# ECGAquisitionBoard.net
KiCad netlist of a schematic drawn in Altium Designer
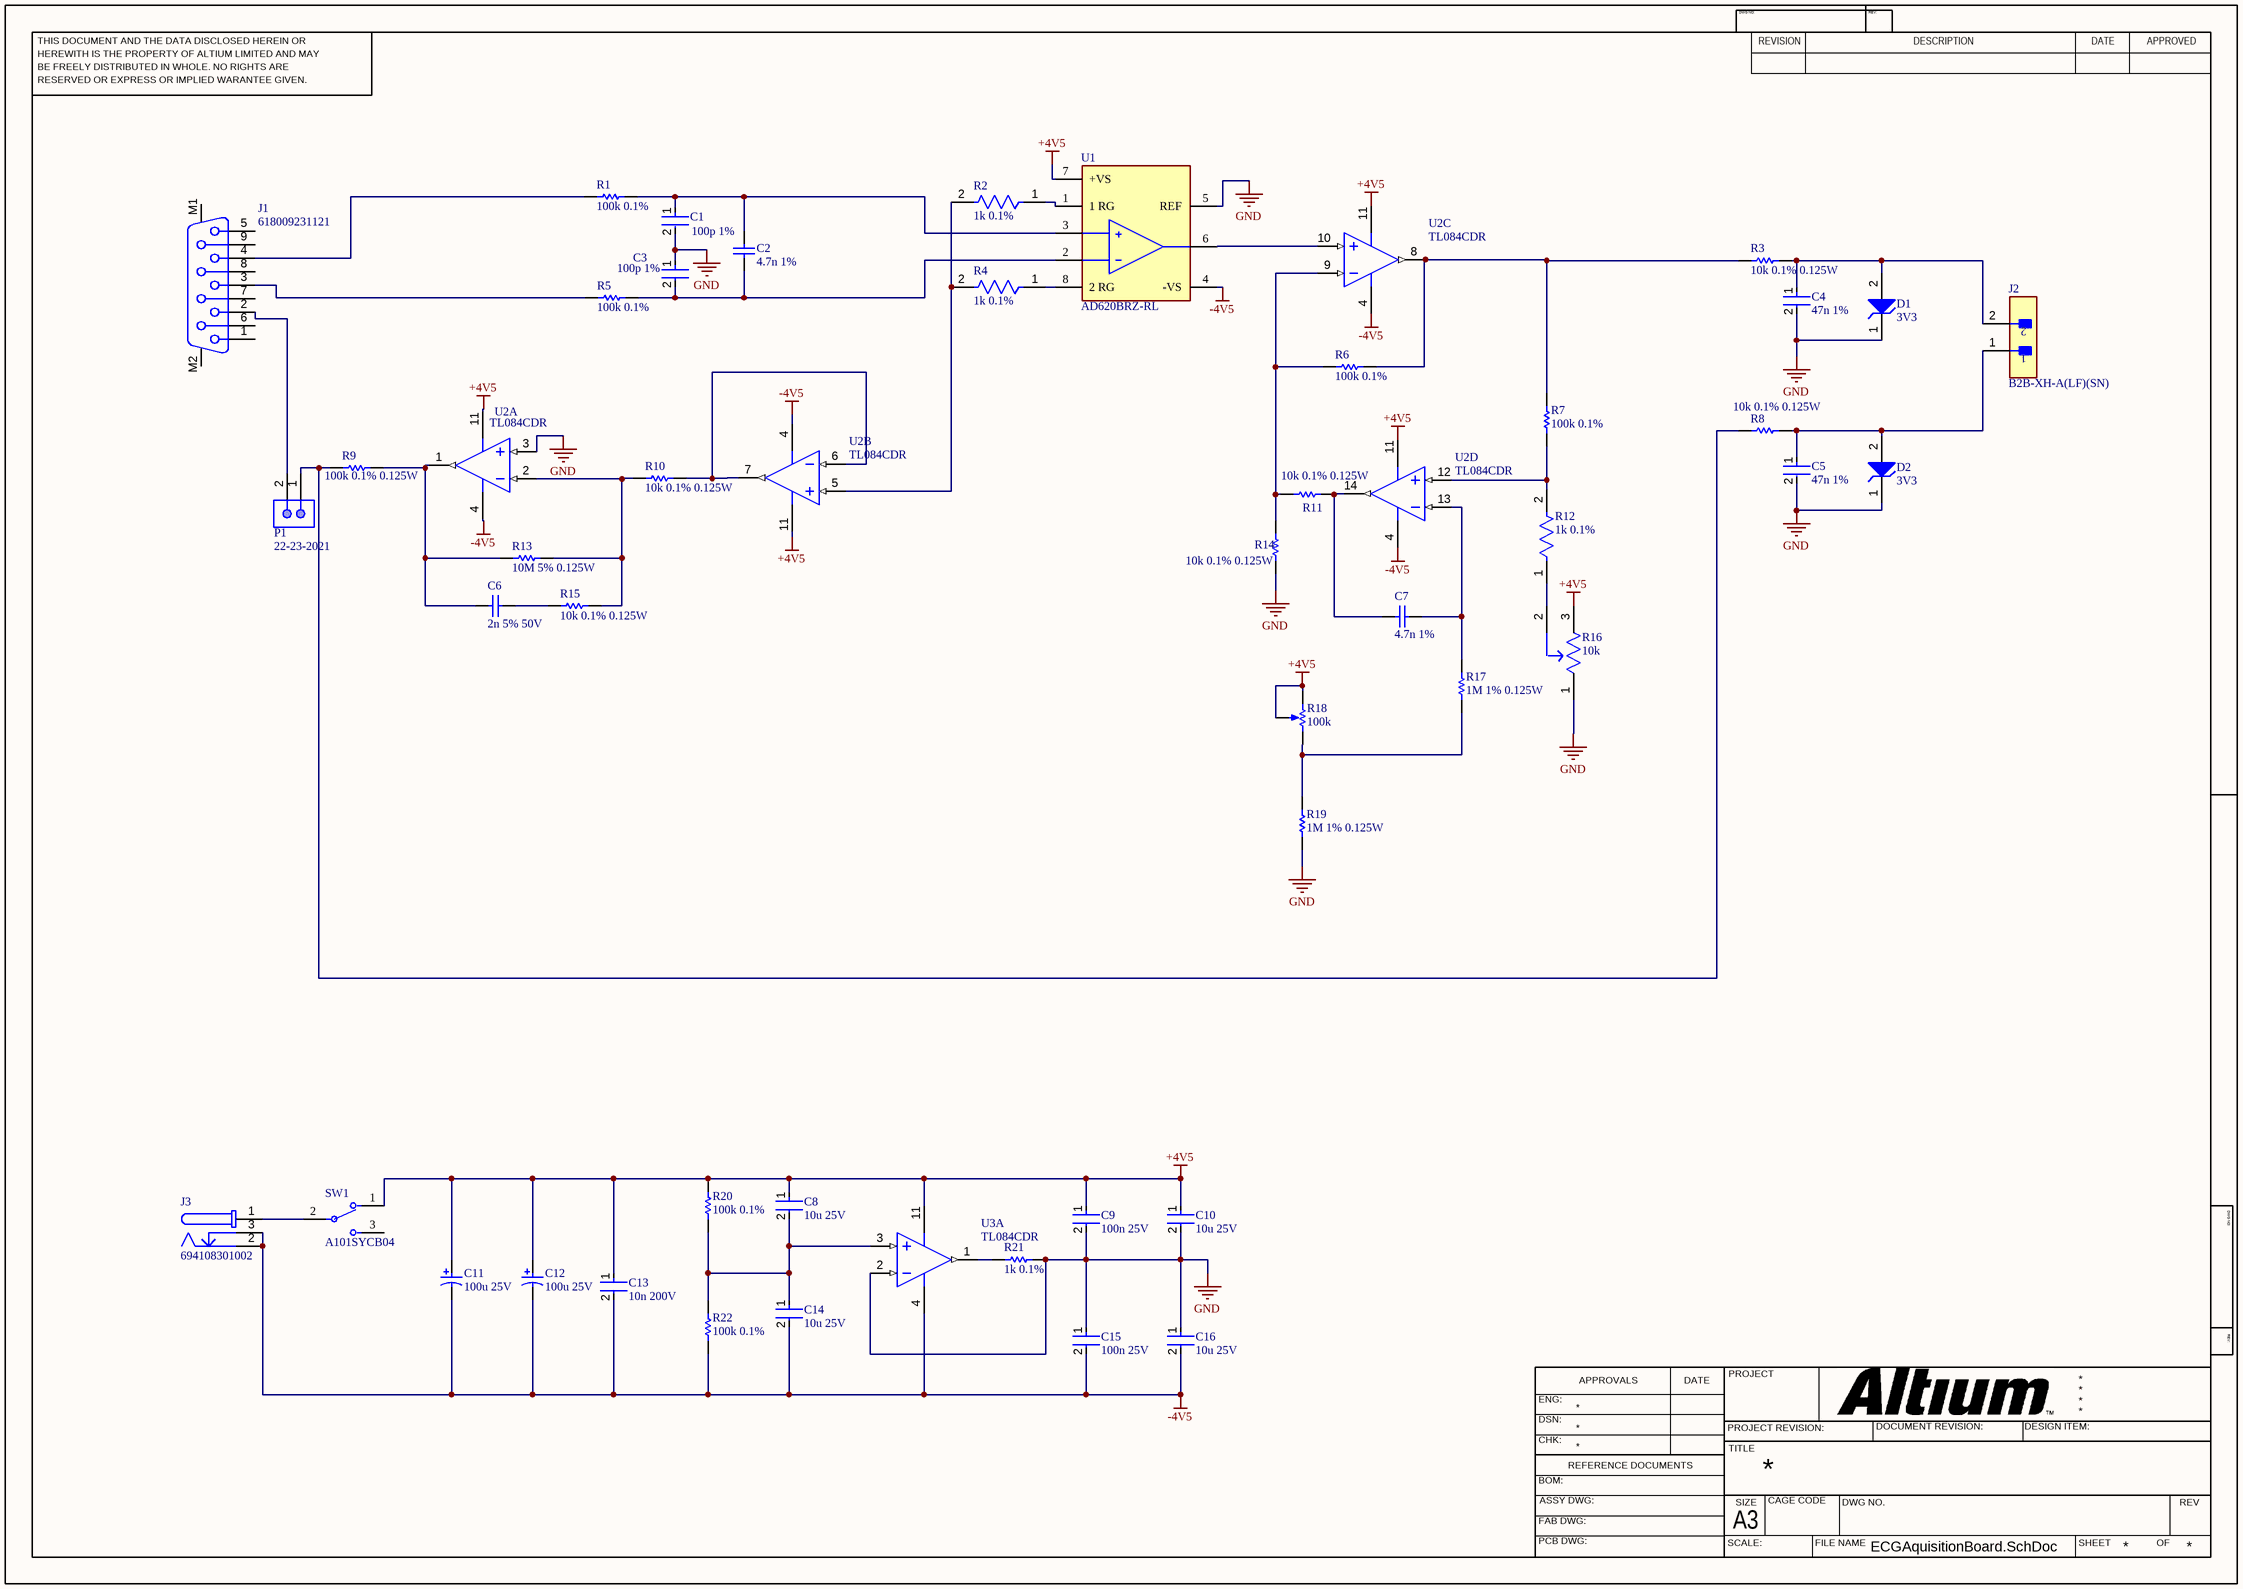
[diagram p0: ECGAquisitionBoard.SchDoc]

(export (version "E")
  (design (tool "Eeschema 10.0.6"))
  (components
    (comp (ref "C1")
      (value "100p 1%")
      (footprint "FP-0805-L_2_01_0_2-W_1_25-IPC_B")
      (description "General Purpose Ceramic Capacitor, 0805, 100pF, 1%, C0G, 30ppm/°C, 100V")
      (fields (field (name "TOLERANCE") "1%") (field (name "VOLTAGE") "100V"))
      (libsource (lib "Altium Content Vault") (part "02cd4be3c70576c341d710602a673aa"))
    )
    (comp (ref "C2")
      (value "4.7n 1%")
      (footprint "CAPC2013X94X50ML20T25")
      (fields
        (field (name "PART NUMBER") "08053A472FAT2A")
        (field (name "MANUFACTURER") "AVX Interconnect / Elco")
      )
      (libsource (lib "Altium Content Vault") (part "CAP"))
    )
    (comp (ref "C3")
      (value "100p 1%")
      (footprint "FP-0805-L_2_01_0_2-W_1_25-IPC_B")
      (description "General Purpose Ceramic Capacitor, 0805, 100pF, 1%, C0G, 30ppm/°C, 100V")
      (fields (field (name "TOLERANCE") "1%") (field (name "VOLTAGE") "100V"))
      (libsource (lib "Altium Content Vault") (part "02cd4be3c70576c341d710602a673aa"))
    )
    (comp (ref "C4")
      (value "47n 1%")
      (footprint "FP-C1206C-EB-MFG")
      (description "C1206 47,000 pF C0G 1.00% 50 V")
      (fields (field (name "TOLERANCE") "0.01"))
      (libsource (lib "Altium Content Vault") (part "b4654b650e69147ec39a6b967a45e02"))
    )
    (comp (ref "C5")
      (value "47n 1%")
      (footprint "FP-C1206C-EB-MFG")
      (description "C1206 47,000 pF C0G 1.00% 50 V")
      (fields (field (name "TOLERANCE") "0.01"))
      (libsource (lib "Altium Content Vault") (part "b4654b650e69147ec39a6b967a45e02"))
    )
    (comp (ref "C6")
      (value "2n 5% 50V")
      (footprint "CAPC2013X70X45NL10T25")
      (fields (field (name "PART NUMBER") "GRM2165C1H202JA01D") (field (name "MANUFACTURER") "Murata"))
      (libsource (lib "Altium Content Vault") (part "CAP"))
    )
    (comp (ref "C7")
      (value "4.7n 1%")
      (footprint "CAPC2013X94X50ML20T25")
      (fields
        (field (name "PART NUMBER") "08053A472FAT2A")
        (field (name "MANUFACTURER") "AVX Interconnect / Elco")
      )
      (libsource (lib "Altium Content Vault") (part "CAP"))
    )
    (comp (ref "C8")
      (value "10u 25V")
      (footprint "FP-GRM21B-0_15-IPC_C")
      (description "Chip Multilayer Ceramic Capacitors for General Purpose, 0805, 10uF, X5R, 15%, 10%, 25V")
      (fields (field (name "VOLTAGE") "25V") (field (name "TOLERANCE") "10%"))
      (libsource (lib "Altium Content Vault") (part "b4654b650e69147ec39a6b967a45e02"))
    )
    (comp (ref "C9")
      (value "100n 25V")
      (footprint "FP-C0805C-DN-MFG")
      (description "C0805 0.10 μF X7R 30ppm/°C 20.00% 25 V")
      (fields (field (name "TOLERANCE") "0.2"))
      (libsource (lib "Altium Content Vault") (part "b4654b650e69147ec39a6b967a45e02"))
    )
    (comp (ref "C10")
      (value "10u 25V")
      (footprint "FP-GRM21B-0_15-IPC_C")
      (description "Chip Multilayer Ceramic Capacitors for General Purpose, 0805, 10uF, X5R, 15%, 10%, 25V")
      (fields (field (name "VOLTAGE") "25V") (field (name "TOLERANCE") "10%"))
      (libsource (lib "Altium Content Vault") (part "b4654b650e69147ec39a6b967a45e02"))
    )
    (comp (ref "C11")
      (value "100u 25V")
      (footprint "PNSC-FK-V-D8_V")
      (fields (field (name "MANUFACTURER") "Panasonic"))
      (libsource (lib "Altium Content Vault") (part "CAP-P-2"))
    )
    (comp (ref "C12")
      (value "100u 25V")
      (footprint "PNSC-FK-V-D8_V")
      (fields (field (name "MANUFACTURER") "Panasonic"))
      (libsource (lib "Altium Content Vault") (part "CAP-P-2"))
    )
    (comp (ref "C13")
      (value "10n 200V")
      (footprint "FP-0805-L_2_01_0_2-W_1_25-IPC_A")
      (description "General Purpose Ceramic Capacitor, 0805, 10nF, 10%, X7R, 0.15, 200V")
      (fields (field (name "VOLTAGE") "200V") (field (name "TOLERANCE") "10%"))
      (libsource (lib "Altium Content Vault") (part "02cd4be3c70576c341d710602a673aa"))
    )
    (comp (ref "C14")
      (value "10u 25V")
      (footprint "FP-GRM21B-0_15-IPC_C")
      (description "Chip Multilayer Ceramic Capacitors for General Purpose, 0805, 10uF, X5R, 15%, 10%, 25V")
      (fields (field (name "VOLTAGE") "25V") (field (name "TOLERANCE") "10%"))
      (libsource (lib "Altium Content Vault") (part "b4654b650e69147ec39a6b967a45e02"))
    )
    (comp (ref "C15")
      (value "100n 25V")
      (footprint "FP-C0805C-DN-MFG")
      (description "C0805 0.10 μF X7R 30ppm/°C 20.00% 25 V")
      (fields (field (name "TOLERANCE") "0.2"))
      (libsource (lib "Altium Content Vault") (part "b4654b650e69147ec39a6b967a45e02"))
    )
    (comp (ref "C16")
      (value "10u 25V")
      (footprint "FP-GRM21B-0_15-IPC_C")
      (description "Chip Multilayer Ceramic Capacitors for General Purpose, 0805, 10uF, X5R, 15%, 10%, 25V")
      (fields (field (name "VOLTAGE") "25V") (field (name "TOLERANCE") "10%"))
      (libsource (lib "Altium Content Vault") (part "b4654b650e69147ec39a6b967a45e02"))
    )
    (comp (ref "D1")
      (value "3V3")
      (footprint "ONSC-SOD-123-2-425-04_V")
      (description "Zener Voltage Regulator, 500 mW, 2-Pin SOD-123, Pb-Free, Tape and Reel")
      (fields (field (name "PARTNUMBER") "MMSZ5226BT1G") (field (name "MANUFACTURER") "On Semiconductor"))
      (libsource (lib "Altium Content Vault") (part "ONSC-K1A2-2"))
    )
    (comp (ref "D2")
      (value "3V3")
      (footprint "ONSC-SOD-123-2-425-04_V")
      (description "Zener Voltage Regulator, 500 mW, 2-Pin SOD-123, Pb-Free, Tape and Reel")
      (fields (field (name "PARTNUMBER") "MMSZ5226BT1G") (field (name "MANUFACTURER") "On Semiconductor"))
      (libsource (lib "Altium Content Vault") (part "ONSC-K1A2-2"))
    )
    (comp (ref "J1")
      (value "618009231121")
      (footprint "618009231121")
      (libsource (lib "Altium Content Vault") (part "D-Sub_Female_09p"))
    )
    (comp (ref "J2")
      (value "B2B-XH-A(LF)(SN)")
      (footprint "FP-B2B-XH-A_LF_SN-MFG")
      (description "CONN HEADER VERT 2POS 2.5MM")
      (libsource (lib "Altium Content Vault") (part "3bc925449376181038e59eaffc5286c"))
    )
    (comp (ref "J3")
      (value "694108301002")
      (footprint "694108301002")
      (libsource (lib "Altium Content Vault") (part "DC Power Jack"))
    )
    (comp (ref "P1")
      (value "22-23-2021")
      (footprint "MOLX-22-23-2021_V")
      (libsource (lib "Altium Content Vault") (part "CN-1P-M-R2"))
    )
    (comp (ref "R1")
      (value "100k 0.1%")
      (footprint "RESC2013X60X40LL20T25_A")
      (fields (field (name "TOLERANCE") "0.1%") (field (name "MANUFACTURER") "Panasonic"))
      (libsource (lib "Altium Content Vault") (part "RES-2"))
    )
    (comp (ref "R2")
      (value "1k 0.1%")
      (footprint "FP-ERA6A-IPC_C")
      (description "RES 1K OHM 0.1% 1/8W 0805")
      (fields (field (name "TOLERANCE") "0.1%"))
      (libsource (lib "Altium Content Vault") (part "1029c3af85768c4190bb7ad29bc67b5"))
    )
    (comp (ref "R3")
      (value "10k 0.1% 0.125W")
      (footprint "RESC2013X60X40LL20T25_A")
      (fields (field (name "TOLERANCE") "0.1%") (field (name "MANUFACTURER") "Panasonic"))
      (libsource (lib "Altium Content Vault") (part "RES-2"))
    )
    (comp (ref "R4")
      (value "1k 0.1%")
      (footprint "FP-ERA6A-IPC_C")
      (description "RES 1K OHM 0.1% 1/8W 0805")
      (fields (field (name "TOLERANCE") "0.1%"))
      (libsource (lib "Altium Content Vault") (part "1029c3af85768c4190bb7ad29bc67b5"))
    )
    (comp (ref "R5")
      (value "100k 0.1%")
      (footprint "RESC2013X60X40LL20T25_A")
      (fields (field (name "TOLERANCE") "0.1%") (field (name "MANUFACTURER") "Panasonic"))
      (libsource (lib "Altium Content Vault") (part "RES-2"))
    )
    (comp (ref "R6")
      (value "100k 0.1%")
      (footprint "RESC2013X60X40LL20T25_A")
      (fields (field (name "TOLERANCE") "0.1%") (field (name "MANUFACTURER") "Panasonic"))
      (libsource (lib "Altium Content Vault") (part "RES-2"))
    )
    (comp (ref "R7")
      (value "100k 0.1%")
      (footprint "RESC2013X60X40LL20T25_A")
      (fields (field (name "TOLERANCE") "0.1%") (field (name "MANUFACTURER") "Panasonic"))
      (libsource (lib "Altium Content Vault") (part "RES-2"))
    )
    (comp (ref "R8")
      (value "10k 0.1% 0.125W")
      (footprint "RESC2013X60X40LL20T25_A")
      (fields (field (name "TOLERANCE") "0.1%") (field (name "MANUFACTURER") "Panasonic"))
      (libsource (lib "Altium Content Vault") (part "RES-2"))
    )
    (comp (ref "R9")
      (value "100k 0.1% 0.125W")
      (footprint "RESC2013X60X40LL20T25_A")
      (fields (field (name "TOLERANCE") "0.1%") (field (name "MANUFACTURER") "Panasonic"))
      (libsource (lib "Altium Content Vault") (part "RES-2"))
    )
    (comp (ref "R10")
      (value "10k 0.1% 0.125W")
      (footprint "RESC2013X60X40LL20T25_A")
      (fields (field (name "TOLERANCE") "0.1%") (field (name "MANUFACTURER") "Panasonic"))
      (libsource (lib "Altium Content Vault") (part "RES-2"))
    )
    (comp (ref "R11")
      (value "10k 0.1% 0.125W")
      (footprint "RESC2013X60X40LL20T25_A")
      (fields (field (name "TOLERANCE") "0.1%") (field (name "MANUFACTURER") "Panasonic"))
      (libsource (lib "Altium Content Vault") (part "RES-2"))
    )
    (comp (ref "R12")
      (value "1k 0.1%")
      (footprint "FP-ERA6A-IPC_C")
      (description "RES 1K OHM 0.1% 1/8W 0805")
      (fields (field (name "TOLERANCE") "0.1%"))
      (libsource (lib "Altium Content Vault") (part "1029c3af85768c4190bb7ad29bc67b5"))
    )
    (comp (ref "R13")
      (value "10M 5% 0.125W")
      (footprint "RESC2013X50X30LL20T20")
      (fields (field (name "PART NUMBER") "CRCW080510M0JNEA") (field (name "MANUFACTURER") "Vishay Dale"))
      (libsource (lib "Altium Content Vault") (part "RES"))
    )
    (comp (ref "R14")
      (value "10k 0.1% 0.125W")
      (footprint "RESC2013X60X40LL20T25_A")
      (fields (field (name "TOLERANCE") "0.1%") (field (name "MANUFACTURER") "Panasonic"))
      (libsource (lib "Altium Content Vault") (part "RES-2"))
    )
    (comp (ref "R15")
      (value "10k 0.1% 0.125W")
      (footprint "RESC2013X60X40LL20T25_A")
      (fields (field (name "TOLERANCE") "0.1%") (field (name "MANUFACTURER") "Panasonic"))
      (libsource (lib "Altium Content Vault") (part "RES-2"))
    )
    (comp (ref "R16")
      (value "10k")
      (footprint "FP-3266W-MFG")
      (description "TRIMMER 10K OHM 0.25W PC PIN TOP")
      (fields
        (field (name "MANUFACTURER") "Bourns")
        (field (name "OCTOPART") "https://octopart.com/3266w-1-103lf-bourns-81445")
      )
      (libsource (lib "Altium Content Vault") (part "5aa38b60e553f01fbee9df648f8b81b"))
    )
    (comp (ref "R17")
      (value "1M 1% 0.125W")
      (footprint "RESC3216X70X50NL05T20")
      (fields (field (name "PART NUMBER") "ERJ-8ENF1004V") (field (name "MANUFACTURER") "Panasonic"))
      (libsource (lib "Altium Content Vault") (part "RES"))
    )
    (comp (ref "R18")
      (value "100k")
      (footprint "BOUR-3266W-3_V")
      (description "Square Trimpot Trimming Potentiometer, 100 KOhm, 0.25 W, -55 to 125 degC, 3-Pin THD, RoHS, Tube")
      (fields (field (name "TOLERANCE") "+/-10%") (field (name "MANUFACTURER") "Bourns"))
      (libsource (lib "Altium Content Vault") (part "BOUR-POT-3"))
    )
    (comp (ref "R19")
      (value "1M 1% 0.125W")
      (footprint "RESC3216X70X50NL05T20")
      (fields (field (name "PART NUMBER") "ERJ-8ENF1004V") (field (name "MANUFACTURER") "Panasonic"))
      (libsource (lib "Altium Content Vault") (part "RES"))
    )
    (comp (ref "R20")
      (value "100k 0.1%")
      (footprint "RESC2013X60X40LL20T25_A")
      (fields (field (name "TOLERANCE") "0.1%") (field (name "MANUFACTURER") "Panasonic"))
      (libsource (lib "Altium Content Vault") (part "RES-2"))
    )
    (comp (ref "R21")
      (value "1k 0.1%")
      (footprint "RESC2013X60X40LL20T25_A")
      (fields (field (name "TOLERANCE") "0.1%") (field (name "MANUFACTURER") "Panasonic"))
      (libsource (lib "Altium Content Vault") (part "RES-2"))
    )
    (comp (ref "R22")
      (value "100k 0.1%")
      (footprint "RESC2013X60X40LL20T25_A")
      (fields (field (name "TOLERANCE") "0.1%") (field (name "MANUFACTURER") "Panasonic"))
      (libsource (lib "Altium Content Vault") (part "RES-2"))
    )
    (comp (ref "SW1")
      (value "A101SYCB04")
      (footprint "FP-A101SYCB04-MFG")
      (description "SWITCH TOGGLE SPDT 0.4VA 20V")
      (libsource (lib "Altium Content Vault") (part "52c419afdc2a387c7d548259a9aeefb"))
    )
    (comp (ref "U1")
      (value "AD620BRZ-RL")
      (footprint "FP-R-8-IPC_A")
      (description "IC INST AMP 1 CIRCUIT 8SOIC")
      (libsource (lib "Altium Content Vault") (part "b1ca39593d8cc57aa2599e6d86efae1"))
    )
    (comp (ref "U2")
      (value "TL084CDR")
      (footprint "D0014A_N")
      (fields (field (name "MANUFACTURER") "Texas Instruments"))
      (libsource (lib "Altium Content Vault") (part "TI-TLXX4X_MC3403-X14"))
    )
    (comp (ref "U3")
      (value "TL084CDR")
      (footprint "D0014A_N")
      (fields (field (name "MANUFACTURER") "Texas Instruments"))
      (libsource (lib "Altium Content Vault") (part "TI-TLXX4X_MC3403-X14"))
    )
  )
  (nets
    (net (code "1") (name "+4V5") (class "Default")
      (node (ref "C10") (pin "1") (pinfunction "1_1") (pintype "passive"))
      (node (ref "C11") (pin "1") (pinfunction "1_1") (pintype "passive"))
      (node (ref "C12") (pin "1") (pinfunction "1_1") (pintype "passive"))
      (node (ref "C13") (pin "1") (pinfunction "1_1") (pintype "passive"))
      (node (ref "C8") (pin "1") (pinfunction "1_1") (pintype "passive"))
      (node (ref "C9") (pin "1") (pinfunction "1_1") (pintype "passive"))
      (node (ref "R16") (pin "3") (pinfunction "CW_3") (pintype "passive"))
      (node (ref "R18") (pin "1") (pinfunction "CCW_1") (pintype "passive"))
      (node (ref "R18") (pin "2") (pinfunction "WIPER_2") (pintype "passive"))
      (node (ref "R20") (pin "2") (pinfunction "2_2") (pintype "passive"))
      (node (ref "SW1") (pin "1") (pinfunction "1_1") (pintype "passive"))
      (node (ref "U1") (pin "7") (pinfunction "+VS_7") (pintype "power_in"))
      (node (ref "U2") (pin "11") (pinfunction "VCC-_11") (pintype "power_in"))
      (node (ref "U3") (pin "11") (pinfunction "VCC-_11") (pintype "power_in"))
    )
    (net (code "2") (name "-4V5") (class "Default")
      (node (ref "C11") (pin "2") (pinfunction "2_2") (pintype "passive"))
      (node (ref "C12") (pin "2") (pinfunction "2_2") (pintype "passive"))
      (node (ref "C13") (pin "2") (pinfunction "2_2") (pintype "passive"))
      (node (ref "C14") (pin "2") (pinfunction "2_2") (pintype "passive"))
      (node (ref "C15") (pin "2") (pinfunction "2_2") (pintype "passive"))
      (node (ref "C16") (pin "2") (pinfunction "2_2") (pintype "passive"))
      (node (ref "J3") (pin "2") (pinfunction "2_2") (pintype "passive"))
      (node (ref "J3") (pin "3") (pinfunction "3_3") (pintype "passive"))
      (node (ref "R22") (pin "1") (pinfunction "1_1") (pintype "passive"))
      (node (ref "U1") (pin "4") (pinfunction "-VS_4") (pintype "power_in"))
      (node (ref "U2") (pin "4") (pinfunction "VCC+_4") (pintype "power_in"))
      (node (ref "U3") (pin "4") (pinfunction "VCC+_4") (pintype "power_in"))
    )
    (net (code "3") (name "GND") (class "Default")
      (node (ref "C1") (pin "2") (pinfunction "2_2") (pintype "passive"))
      (node (ref "C10") (pin "2") (pinfunction "2_2") (pintype "passive"))
      (node (ref "C15") (pin "1") (pinfunction "1_1") (pintype "passive"))
      (node (ref "C16") (pin "1") (pinfunction "1_1") (pintype "passive"))
      (node (ref "C3") (pin "1") (pinfunction "1_1") (pintype "passive"))
      (node (ref "C4") (pin "2") (pinfunction "2_2") (pintype "passive"))
      (node (ref "C5") (pin "2") (pinfunction "2_2") (pintype "passive"))
      (node (ref "C9") (pin "2") (pinfunction "2_2") (pintype "passive"))
      (node (ref "D1") (pin "1") (pinfunction "K_1") (pintype "passive"))
      (node (ref "D2") (pin "1") (pinfunction "K_1") (pintype "passive"))
      (node (ref "R14") (pin "1") (pinfunction "1_1") (pintype "passive"))
      (node (ref "R16") (pin "1") (pinfunction "CCW_1") (pintype "passive"))
      (node (ref "R19") (pin "1") (pinfunction "1_1") (pintype "passive"))
      (node (ref "R21") (pin "1") (pinfunction "1_1") (pintype "passive"))
      (node (ref "U1") (pin "5") (pinfunction "REF_5") (pintype "passive"))
      (node (ref "U2") (pin "3") (pinfunction "IN1+_3") (pintype "input"))
      (node (ref "U3") (pin "2") (pinfunction "IN1-_2") (pintype "input"))
    )
    (net (code "4") (name "Net-(C6-Pad2)") (class "Default")
      (node (ref "C6") (pin "2") (pinfunction "2_2") (pintype "passive"))
      (node (ref "R15") (pin "2") (pinfunction "2_2") (pintype "passive"))
    )
    (net (code "5") (name "Net-(D1-A)") (class "Default")
      (node (ref "C4") (pin "1") (pinfunction "1_1") (pintype "passive"))
      (node (ref "D1") (pin "2") (pinfunction "A_2") (pintype "passive"))
      (node (ref "J2") (pin "2") (pinfunction "2_2") (pintype "passive"))
      (node (ref "R3") (pin "1") (pinfunction "1_1") (pintype "passive"))
    )
    (net (code "6") (name "Net-(D2-A)") (class "Default")
      (node (ref "C5") (pin "1") (pinfunction "1_1") (pintype "passive"))
      (node (ref "D2") (pin "2") (pinfunction "A_2") (pintype "passive"))
      (node (ref "J2") (pin "1") (pinfunction "1_1") (pintype "passive"))
      (node (ref "R8") (pin "1") (pinfunction "1_1") (pintype "passive"))
    )
    (net (code "7") (name "Net-(J1-Pad2)") (class "Default")
      (node (ref "J1") (pin "2") (pinfunction "2_2") (pintype "passive"))
      (node (ref "P1") (pin "2") (pinfunction "2_2") (pintype "passive"))
    )
    (net (code "8") (name "Net-(J1-Pad3)") (class "Default")
      (node (ref "J1") (pin "3") (pinfunction "3_3") (pintype "passive"))
      (node (ref "R5") (pin "2") (pinfunction "2_2") (pintype "passive"))
    )
    (net (code "9") (name "Net-(J1-Pad4)") (class "Default")
      (node (ref "J1") (pin "4") (pinfunction "4_4") (pintype "passive"))
      (node (ref "R1") (pin "2") (pinfunction "2_2") (pintype "passive"))
    )
    (net (code "10") (name "Net-(J3-Pad1)") (class "Default")
      (node (ref "J3") (pin "1") (pinfunction "1_1") (pintype "passive"))
      (node (ref "SW1") (pin "2") (pinfunction "2_2") (pintype "passive"))
    )
    (net (code "11") (name "Net-(P1-Pad1)") (class "Default")
      (node (ref "P1") (pin "1") (pinfunction "1_1") (pintype "passive"))
      (node (ref "R8") (pin "2") (pinfunction "2_2") (pintype "passive"))
      (node (ref "R9") (pin "2") (pinfunction "2_2") (pintype "passive"))
    )
    (net (code "12") (name "Net-(R16-WIPER)") (class "Default")
      (node (ref "R12") (pin "1") (pinfunction "1_1") (pintype "passive"))
      (node (ref "R16") (pin "2") (pinfunction "WIPER_2") (pintype "passive"))
    )
    (net (code "13") (name "Net-(R18-CW)") (class "Default")
      (node (ref "R17") (pin "1") (pinfunction "1_1") (pintype "passive"))
      (node (ref "R18") (pin "3") (pinfunction "CW_3") (pintype "passive"))
      (node (ref "R19") (pin "2") (pinfunction "2_2") (pintype "passive"))
    )
    (net (code "14") (name "Net-(U1-+IN)") (class "Default")
      (node (ref "C1") (pin "1") (pinfunction "1_1") (pintype "passive"))
      (node (ref "C2") (pin "2") (pinfunction "2_2") (pintype "passive"))
      (node (ref "R1") (pin "1") (pinfunction "1_1") (pintype "passive"))
      (node (ref "U1") (pin "3") (pinfunction "+IN_3") (pintype "tri_state"))
    )
    (net (code "15") (name "Net-(U1--IN)") (class "Default")
      (node (ref "C2") (pin "1") (pinfunction "1_1") (pintype "passive"))
      (node (ref "C3") (pin "2") (pinfunction "2_2") (pintype "passive"))
      (node (ref "R5") (pin "1") (pinfunction "1_1") (pintype "passive"))
      (node (ref "U1") (pin "2") (pinfunction "-IN_2") (pintype "tri_state"))
    )
    (net (code "16") (name "Net-(U1-1_RG)") (class "Default")
      (node (ref "R2") (pin "1") (pinfunction "1_1") (pintype "passive"))
      (node (ref "U1") (pin "1") (pinfunction "1_RG_1") (pintype "passive"))
    )
    (net (code "17") (name "Net-(U1-2_RG)") (class "Default")
      (node (ref "R4") (pin "1") (pinfunction "1_1") (pintype "passive"))
      (node (ref "U1") (pin "8") (pinfunction "2_RG_8") (pintype "passive"))
    )
    (net (code "18") (name "Net-(U1-OUTPUT)") (class "Default")
      (node (ref "U1") (pin "6") (pinfunction "OUTPUT_6") (pintype "passive"))
      (node (ref "U2") (pin "10") (pinfunction "IN3+_10") (pintype "input"))
    )
    (net (code "19") (name "Net-(U2A-IN1-)") (class "Default")
      (node (ref "R10") (pin "2") (pinfunction "2_2") (pintype "passive"))
      (node (ref "R13") (pin "2") (pinfunction "2_2") (pintype "passive"))
      (node (ref "R15") (pin "1") (pinfunction "1_1") (pintype "passive"))
      (node (ref "U2") (pin "2") (pinfunction "IN1-_2") (pintype "input"))
    )
    (net (code "20") (name "Net-(U2A-OUT1)") (class "Default")
      (node (ref "C6") (pin "1") (pinfunction "1_1") (pintype "passive"))
      (node (ref "R13") (pin "1") (pinfunction "1_1") (pintype "passive"))
      (node (ref "R9") (pin "1") (pinfunction "1_1") (pintype "passive"))
      (node (ref "U2") (pin "1") (pinfunction "OUT1_1") (pintype "output"))
    )
    (net (code "21") (name "Net-(U2B-IN2+)") (class "Default")
      (node (ref "R2") (pin "2") (pinfunction "2_2") (pintype "passive"))
      (node (ref "R4") (pin "2") (pinfunction "2_2") (pintype "passive"))
      (node (ref "U2") (pin "5") (pinfunction "IN2+_5") (pintype "input"))
    )
    (net (code "22") (name "Net-(U2B-IN2-)") (class "Default")
      (node (ref "R10") (pin "1") (pinfunction "1_1") (pintype "passive"))
      (node (ref "U2") (pin "6") (pinfunction "IN2-_6") (pintype "input"))
      (node (ref "U2") (pin "7") (pinfunction "OUT2_7") (pintype "output"))
    )
    (net (code "23") (name "Net-(U2C-IN3-)") (class "Default")
      (node (ref "R11") (pin "2") (pinfunction "2_2") (pintype "passive"))
      (node (ref "R14") (pin "2") (pinfunction "2_2") (pintype "passive"))
      (node (ref "R6") (pin "2") (pinfunction "2_2") (pintype "passive"))
      (node (ref "U2") (pin "9") (pinfunction "IN3-_9") (pintype "input"))
    )
    (net (code "24") (name "Net-(U2C-OUT3)") (class "Default")
      (node (ref "R3") (pin "2") (pinfunction "2_2") (pintype "passive"))
      (node (ref "R6") (pin "1") (pinfunction "1_1") (pintype "passive"))
      (node (ref "R7") (pin "1") (pinfunction "1_1") (pintype "passive"))
      (node (ref "U2") (pin "8") (pinfunction "OUT3_8") (pintype "output"))
    )
    (net (code "25") (name "Net-(U2D-IN4+)") (class "Default")
      (node (ref "R12") (pin "2") (pinfunction "2_2") (pintype "passive"))
      (node (ref "R7") (pin "2") (pinfunction "2_2") (pintype "passive"))
      (node (ref "U2") (pin "12") (pinfunction "IN4+_12") (pintype "input"))
    )
    (net (code "26") (name "Net-(U2D-IN4-)") (class "Default")
      (node (ref "C7") (pin "1") (pinfunction "1_1") (pintype "passive"))
      (node (ref "R17") (pin "2") (pinfunction "2_2") (pintype "passive"))
      (node (ref "U2") (pin "13") (pinfunction "IN4-_13") (pintype "input"))
    )
    (net (code "27") (name "Net-(U2D-OUT4)") (class "Default")
      (node (ref "C7") (pin "2") (pinfunction "2_2") (pintype "passive"))
      (node (ref "R11") (pin "1") (pinfunction "1_1") (pintype "passive"))
      (node (ref "U2") (pin "14") (pinfunction "OUT4_14") (pintype "output"))
    )
    (net (code "28") (name "Net-(U3A-IN1+)") (class "Default")
      (node (ref "C14") (pin "1") (pinfunction "1_1") (pintype "passive"))
      (node (ref "C8") (pin "2") (pinfunction "2_2") (pintype "passive"))
      (node (ref "R20") (pin "1") (pinfunction "1_1") (pintype "passive"))
      (node (ref "R22") (pin "2") (pinfunction "2_2") (pintype "passive"))
      (node (ref "U3") (pin "3") (pinfunction "IN1+_3") (pintype "input"))
    )
    (net (code "29") (name "Net-(U3A-OUT1)") (class "Default")
      (node (ref "R21") (pin "2") (pinfunction "2_2") (pintype "passive"))
      (node (ref "U3") (pin "1") (pinfunction "OUT1_1") (pintype "output"))
    )
    (net (code "30") (name "unconnected-(J1-Pad1)") (class "Default")
      (node (ref "J1") (pin "1") (pinfunction "1_1") (pintype "passive"))
    )
    (net (code "31") (name "unconnected-(J1-Pad5)") (class "Default")
      (node (ref "J1") (pin "5") (pinfunction "5_5") (pintype "passive"))
    )
    (net (code "32") (name "unconnected-(J1-Pad6)") (class "Default")
      (node (ref "J1") (pin "6") (pinfunction "6_6") (pintype "passive"))
    )
    (net (code "33") (name "unconnected-(J1-Pad7)") (class "Default")
      (node (ref "J1") (pin "7") (pinfunction "7_7") (pintype "passive"))
    )
    (net (code "34") (name "unconnected-(J1-Pad8)") (class "Default")
      (node (ref "J1") (pin "8") (pinfunction "8_8") (pintype "passive"))
    )
    (net (code "35") (name "unconnected-(J1-Pad9)") (class "Default")
      (node (ref "J1") (pin "9") (pinfunction "9_9") (pintype "passive"))
    )
    (net (code "36") (name "unconnected-(J1-PadM1)") (class "Default")
      (node (ref "J1") (pin "M1") (pinfunction "M1_M1") (pintype "passive"))
    )
    (net (code "37") (name "unconnected-(J1-PadM2)") (class "Default")
      (node (ref "J1") (pin "M2") (pinfunction "M2_M2") (pintype "passive"))
    )
    (net (code "38") (name "unconnected-(SW1-Pad3)") (class "Default")
      (node (ref "SW1") (pin "3") (pinfunction "3_3") (pintype "passive"))
    )
  )
)
